# io-headers.net
KiCad netlist of a schematic drawn in Altium Designer
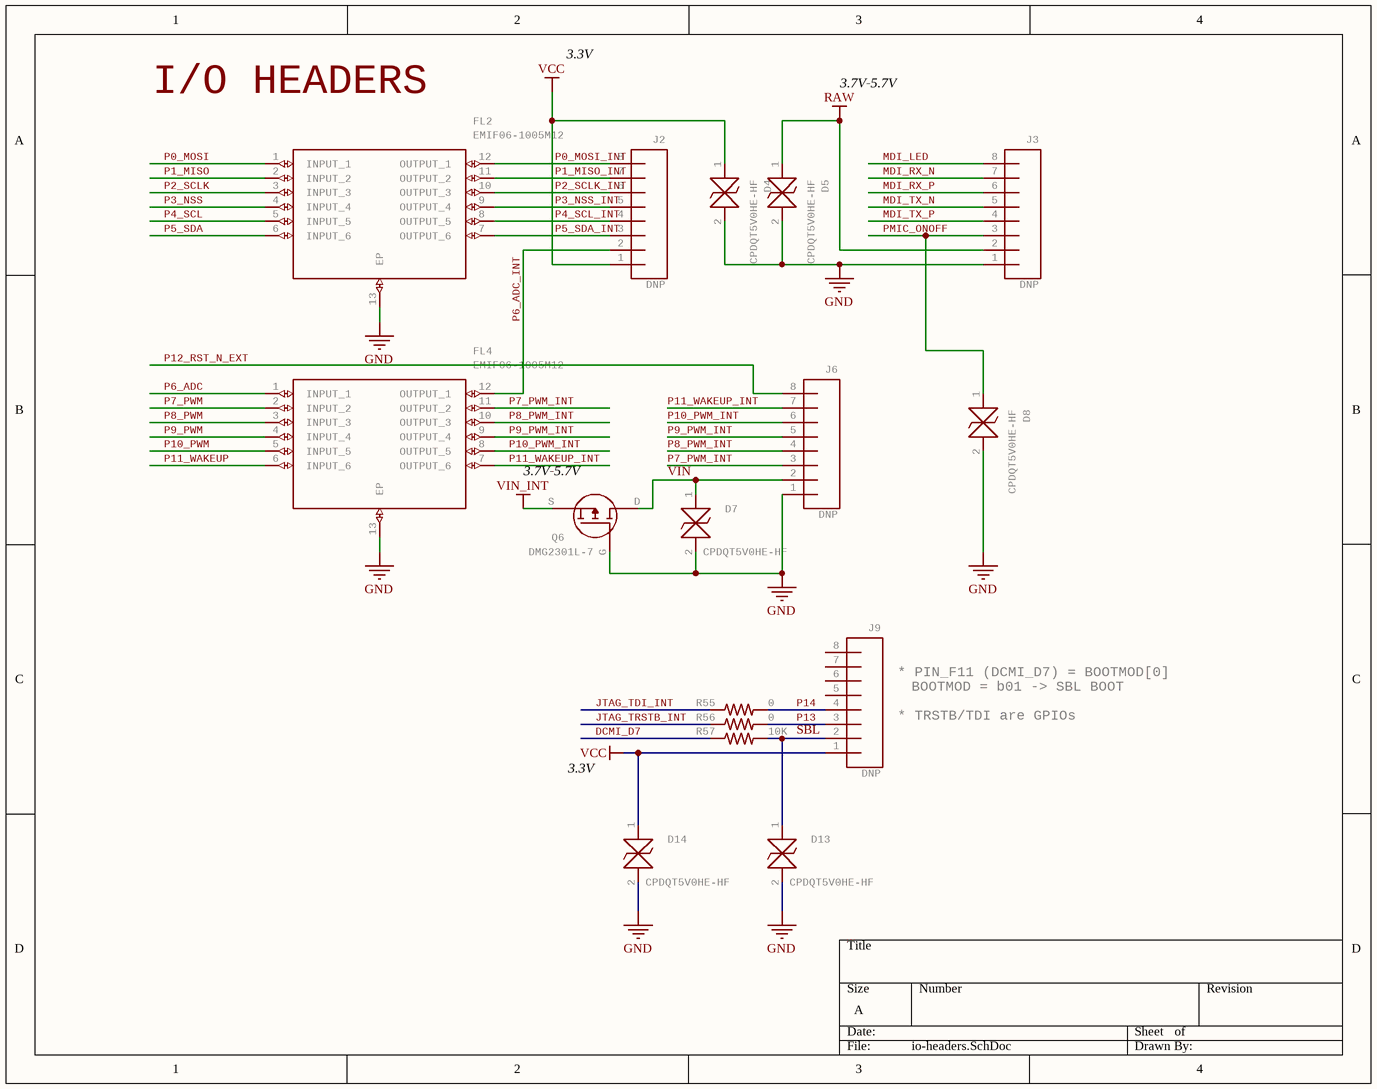
[diagram p0: io-headers.SchDoc]

(export (version "E")
  (design (tool "Eeschema 10.0.6"))
  (components
    (comp (ref "D4")
      (value "CPDQT5V0HE-HF")
      (footprint "CPDQT5V0HEHF")
      (description "ESD Suppressors / TVS Diodes DIODE ESD 5VWM 65W 0402/SOD-923F   Source:  Datasheet")
      (fields (field (name "MOUSER_PART_NUMBER") "MOUSER_PART_NUMBER"))
      (libsource (lib "rt10") (part "CPDQT5V0HE-HF"))
    )
    (comp (ref "D5")
      (value "CPDQT5V0HE-HF")
      (footprint "CPDQT5V0HEHF")
      (description "ESD Suppressors / TVS Diodes DIODE ESD 5VWM 65W 0402/SOD-923F   Source:  Datasheet")
      (fields (field (name "MOUSER_PART_NUMBER") "MOUSER_PART_NUMBER"))
      (libsource (lib "rt10") (part "CPDQT5V0HE-HF"))
    )
    (comp (ref "D7")
      (value "CPDQT5V0HE-HF")
      (footprint "CPDQT5V0HEHF")
      (description "ESD Suppressors / TVS Diodes DIODE ESD 5VWM 65W 0402/SOD-923F   Source:  Datasheet")
      (fields (field (name "MOUSER_PART_NUMBER") "MOUSER_PART_NUMBER"))
      (libsource (lib "rt10") (part "CPDQT5V0HE-HF"))
    )
    (comp (ref "D8")
      (value "CPDQT5V0HE-HF")
      (footprint "CPDQT5V0HEHF")
      (description "ESD Suppressors / TVS Diodes DIODE ESD 5VWM 65W 0402/SOD-923F   Source:  Datasheet")
      (fields (field (name "MOUSER_PART_NUMBER") "MOUSER_PART_NUMBER"))
      (libsource (lib "rt10") (part "CPDQT5V0HE-HF"))
    )
    (comp (ref "D13")
      (value "CPDQT5V0HE-HF")
      (footprint "CPDQT5V0HEHF")
      (description "ESD Suppressors / TVS Diodes DIODE ESD 5VWM 65W 0402/SOD-923F   Source:  Datasheet")
      (fields (field (name "MOUSER_PART_NUMBER") "MOUSER_PART_NUMBER"))
      (libsource (lib "rt10") (part "CPDQT5V0HE-HF"))
    )
    (comp (ref "D14")
      (value "CPDQT5V0HE-HF")
      (footprint "CPDQT5V0HEHF")
      (description "ESD Suppressors / TVS Diodes DIODE ESD 5VWM 65W 0402/SOD-923F   Source:  Datasheet")
      (fields (field (name "MOUSER_PART_NUMBER") "MOUSER_PART_NUMBER"))
      (libsource (lib "rt10") (part "CPDQT5V0HE-HF"))
    )
    (comp (ref "FL2")
      (value "EMIF06-1005M12")
      (footprint "SON40P150X250X65-13N")
      (description "EMI Filter Circuits 6lin lw cpcitnc EMI 45pF -35db @ 900MHz   Source:  Datasheet")
      (fields (field (name "MOUSER_PART_NUMBER") "511-EMIF06-1005M12"))
      (libsource (lib "rt10") (part "EMIF06-1005M12"))
    )
    (comp (ref "FL4")
      (value "EMIF06-1005M12")
      (footprint "SON40P150X250X65-13N")
      (description "EMI Filter Circuits 6lin lw cpcitnc EMI 45pF -35db @ 900MHz   Source:  Datasheet")
      (fields (field (name "MOUSER_PART_NUMBER") "511-EMIF06-1005M12"))
      (libsource (lib "rt10") (part "EMIF06-1005M12"))
    )
    (comp (ref "J2") (value "DNP") (footprint "1X08") (libsource (lib "rt10") (part "CONN_08{dblquote}")))
    (comp (ref "J3") (value "DNP") (footprint "1X08") (libsource (lib "rt10") (part "CONN_08{dblquote}")))
    (comp (ref "J6") (value "DNP") (footprint "1X08") (libsource (lib "rt10") (part "CONN_08{dblquote}")))
    (comp (ref "J9") (value "DNP") (footprint "1X08") (libsource (lib "rt10") (part "CONN_08{dblquote}")))
    (comp (ref "Q6")
      (value "DMG2301L-7")
      (footprint "SOT-23-3-FET")
      (libsource (lib "rt10") (part "DMG2301L-7"))
    )
    (comp (ref "R55")
      (value "0")
      (footprint "0402-RES")
      (description "ResistorBasic schematic elements and footprints for 0603, 1206, and PTH resistors.")
      (fields (field (name "MPN") "RC0402JR-070R"))
      (libsource (lib "rt10") (part "RESISTOR0402-RES"))
    )
    (comp (ref "R56")
      (value "0")
      (footprint "0402-RES")
      (description "ResistorBasic schematic elements and footprints for 0603, 1206, and PTH resistors.")
      (fields (field (name "MPN") "RC0402JR-070R"))
      (libsource (lib "rt10") (part "RESISTOR0402-RES"))
    )
    (comp (ref "R57")
      (value "10K")
      (footprint "0402-RES")
      (description "ResistorBasic schematic elements and footprints for 0603, 1206, and PTH resistors.")
      (fields (field (name "MPN") "AC0402FR-1310K"))
      (libsource (lib "rt10") (part "RESISTOR0402-RES"))
    )
  )
  (nets
    (net (code "1") (name "/DCMI_D7") (class "Default")
      (node (ref "R57") (pin "1") (pinfunction "1_1") (pintype "passive"))
    )
    (net (code "2") (name "/JTAG_TDI_INT") (class "Default")
      (node (ref "R55") (pin "1") (pinfunction "1_1") (pintype "passive"))
    )
    (net (code "3") (name "/JTAG_TRSTB_INT") (class "Default")
      (node (ref "R56") (pin "1") (pinfunction "1_1") (pintype "passive"))
    )
    (net (code "4") (name "/MDI_LED") (class "Default")
      (node (ref "J3") (pin "8") (pinfunction "8_8") (pintype "passive"))
    )
    (net (code "5") (name "/MDI_RX_N") (class "Default")
      (node (ref "J3") (pin "7") (pinfunction "7_7") (pintype "passive"))
    )
    (net (code "6") (name "/MDI_RX_P") (class "Default")
      (node (ref "J3") (pin "6") (pinfunction "6_6") (pintype "passive"))
    )
    (net (code "7") (name "/MDI_TX_N") (class "Default")
      (node (ref "J3") (pin "5") (pinfunction "5_5") (pintype "passive"))
    )
    (net (code "8") (name "/MDI_TX_P") (class "Default")
      (node (ref "J3") (pin "4") (pinfunction "4_4") (pintype "passive"))
    )
    (net (code "9") (name "/P0_MOSI") (class "Default")
      (node (ref "FL2") (pin "1") (pinfunction "INPUT_1_1") (pintype "bidirectional"))
    )
    (net (code "10") (name "/P0_MOSI_INT") (class "Default")
      (node (ref "FL2") (pin "12") (pinfunction "OUTPUT_1_12") (pintype "bidirectional"))
      (node (ref "J2") (pin "8") (pinfunction "8_8") (pintype "passive"))
    )
    (net (code "11") (name "/P1_MISO") (class "Default")
      (node (ref "FL2") (pin "2") (pinfunction "INPUT_2_2") (pintype "bidirectional"))
    )
    (net (code "12") (name "/P1_MISO_INT") (class "Default")
      (node (ref "FL2") (pin "11") (pinfunction "OUTPUT_2_11") (pintype "bidirectional"))
      (node (ref "J2") (pin "7") (pinfunction "7_7") (pintype "passive"))
    )
    (net (code "13") (name "/P2_SCLK") (class "Default")
      (node (ref "FL2") (pin "3") (pinfunction "INPUT_3_3") (pintype "bidirectional"))
    )
    (net (code "14") (name "/P2_SCLK_INT") (class "Default")
      (node (ref "FL2") (pin "10") (pinfunction "OUTPUT_3_10") (pintype "bidirectional"))
      (node (ref "J2") (pin "6") (pinfunction "6_6") (pintype "passive"))
    )
    (net (code "15") (name "/P3_NSS") (class "Default")
      (node (ref "FL2") (pin "4") (pinfunction "INPUT_4_4") (pintype "bidirectional"))
    )
    (net (code "16") (name "/P3_NSS_INT") (class "Default")
      (node (ref "FL2") (pin "9") (pinfunction "OUTPUT_4_9") (pintype "bidirectional"))
      (node (ref "J2") (pin "5") (pinfunction "5_5") (pintype "passive"))
    )
    (net (code "17") (name "/P4_SCL") (class "Default")
      (node (ref "FL2") (pin "5") (pinfunction "INPUT_5_5") (pintype "bidirectional"))
    )
    (net (code "18") (name "/P4_SCL_INT") (class "Default")
      (node (ref "FL2") (pin "8") (pinfunction "OUTPUT_5_8") (pintype "bidirectional"))
      (node (ref "J2") (pin "4") (pinfunction "4_4") (pintype "passive"))
    )
    (net (code "19") (name "/P5_SDA") (class "Default")
      (node (ref "FL2") (pin "6") (pinfunction "INPUT_6_6") (pintype "bidirectional"))
    )
    (net (code "20") (name "/P5_SDA_INT") (class "Default")
      (node (ref "FL2") (pin "7") (pinfunction "OUTPUT_6_7") (pintype "bidirectional"))
      (node (ref "J2") (pin "3") (pinfunction "3_3") (pintype "passive"))
    )
    (net (code "21") (name "/P6_ADC") (class "Default")
      (node (ref "FL4") (pin "1") (pinfunction "INPUT_1_1") (pintype "bidirectional"))
    )
    (net (code "22") (name "/P6_ADC_INT") (class "Default")
      (node (ref "FL4") (pin "12") (pinfunction "OUTPUT_1_12") (pintype "bidirectional"))
      (node (ref "J2") (pin "2") (pinfunction "2_2") (pintype "passive"))
    )
    (net (code "23") (name "/P7_PWM") (class "Default")
      (node (ref "FL4") (pin "2") (pinfunction "INPUT_2_2") (pintype "bidirectional"))
    )
    (net (code "24") (name "/P7_PWM_INT") (class "Default")
      (node (ref "FL4") (pin "11") (pinfunction "OUTPUT_2_11") (pintype "bidirectional"))
      (node (ref "J6") (pin "3") (pinfunction "3_3") (pintype "passive"))
    )
    (net (code "25") (name "/P8_PWM") (class "Default")
      (node (ref "FL4") (pin "3") (pinfunction "INPUT_3_3") (pintype "bidirectional"))
    )
    (net (code "26") (name "/P8_PWM_INT") (class "Default")
      (node (ref "FL4") (pin "10") (pinfunction "OUTPUT_3_10") (pintype "bidirectional"))
      (node (ref "J6") (pin "4") (pinfunction "4_4") (pintype "passive"))
    )
    (net (code "27") (name "/P9_PWM") (class "Default")
      (node (ref "FL4") (pin "4") (pinfunction "INPUT_4_4") (pintype "bidirectional"))
    )
    (net (code "28") (name "/P9_PWM_INT") (class "Default")
      (node (ref "FL4") (pin "9") (pinfunction "OUTPUT_4_9") (pintype "bidirectional"))
      (node (ref "J6") (pin "5") (pinfunction "5_5") (pintype "passive"))
    )
    (net (code "29") (name "/P10_PWM") (class "Default")
      (node (ref "FL4") (pin "5") (pinfunction "INPUT_5_5") (pintype "bidirectional"))
    )
    (net (code "30") (name "/P10_PWM_INT") (class "Default")
      (node (ref "FL4") (pin "8") (pinfunction "OUTPUT_5_8") (pintype "bidirectional"))
      (node (ref "J6") (pin "6") (pinfunction "6_6") (pintype "passive"))
    )
    (net (code "31") (name "/P11_WAKEUP") (class "Default")
      (node (ref "FL4") (pin "6") (pinfunction "INPUT_6_6") (pintype "bidirectional"))
    )
    (net (code "32") (name "/P11_WAKEUP_INT") (class "Default")
      (node (ref "FL4") (pin "7") (pinfunction "OUTPUT_6_7") (pintype "bidirectional"))
      (node (ref "J6") (pin "7") (pinfunction "7_7") (pintype "passive"))
    )
    (net (code "33") (name "/P12_RST_N_EXT") (class "Default")
      (node (ref "J6") (pin "8") (pinfunction "8_8") (pintype "passive"))
    )
    (net (code "34") (name "/P13") (class "Default")
      (node (ref "J9") (pin "3") (pinfunction "3_3") (pintype "passive"))
      (node (ref "R56") (pin "2") (pinfunction "2_2") (pintype "passive"))
    )
    (net (code "35") (name "/P14") (class "Default")
      (node (ref "J9") (pin "4") (pinfunction "4_4") (pintype "passive"))
      (node (ref "R55") (pin "2") (pinfunction "2_2") (pintype "passive"))
    )
    (net (code "36") (name "/PMIC_ONOFF") (class "Default")
      (node (ref "D8") (pin "1") (pinfunction "1_1") (pintype "bidirectional"))
      (node (ref "J3") (pin "3") (pinfunction "3_3") (pintype "passive"))
    )
    (net (code "37") (name "/SBL") (class "Default")
      (node (ref "D13") (pin "1") (pinfunction "1_1") (pintype "bidirectional"))
      (node (ref "J9") (pin "2") (pinfunction "2_2") (pintype "passive"))
      (node (ref "R57") (pin "2") (pinfunction "2_2") (pintype "passive"))
    )
    (net (code "38") (name "/VIN") (class "Default")
      (node (ref "D7") (pin "1") (pinfunction "1_1") (pintype "bidirectional"))
      (node (ref "J6") (pin "2") (pinfunction "2_2") (pintype "passive"))
      (node (ref "Q6") (pin "D") (pinfunction "D_D") (pintype "bidirectional"))
    )
    (net (code "39") (name "GND") (class "Default")
      (node (ref "D13") (pin "2") (pinfunction "2_2") (pintype "bidirectional"))
      (node (ref "D14") (pin "2") (pinfunction "2_2") (pintype "bidirectional"))
      (node (ref "D4") (pin "2") (pinfunction "2_2") (pintype "bidirectional"))
      (node (ref "D5") (pin "2") (pinfunction "2_2") (pintype "bidirectional"))
      (node (ref "D7") (pin "2") (pinfunction "2_2") (pintype "bidirectional"))
      (node (ref "D8") (pin "2") (pinfunction "2_2") (pintype "bidirectional"))
      (node (ref "FL2") (pin "13") (pinfunction "EP_13") (pintype "bidirectional"))
      (node (ref "FL4") (pin "13") (pinfunction "EP_13") (pintype "bidirectional"))
      (node (ref "J3") (pin "1") (pinfunction "1_1") (pintype "passive"))
      (node (ref "J6") (pin "1") (pinfunction "1_1") (pintype "passive"))
      (node (ref "Q6") (pin "G") (pinfunction "G_G") (pintype "bidirectional"))
    )
    (net (code "40") (name "RAW") (class "Default")
      (node (ref "D5") (pin "1") (pinfunction "1_1") (pintype "bidirectional"))
      (node (ref "J3") (pin "2") (pinfunction "2_2") (pintype "passive"))
    )
    (net (code "41") (name "VCC") (class "Default")
      (node (ref "D14") (pin "1") (pinfunction "1_1") (pintype "bidirectional"))
      (node (ref "D4") (pin "1") (pinfunction "1_1") (pintype "bidirectional"))
      (node (ref "J2") (pin "1") (pinfunction "1_1") (pintype "passive"))
      (node (ref "J9") (pin "1") (pinfunction "1_1") (pintype "passive"))
    )
    (net (code "42") (name "VIN_INT") (class "Default")
      (node (ref "Q6") (pin "S") (pinfunction "S_S") (pintype "bidirectional"))
    )
    (net (code "43") (name "unconnected-(J9-Pad5)") (class "Default")
      (node (ref "J9") (pin "5") (pinfunction "5_5") (pintype "passive"))
    )
    (net (code "44") (name "unconnected-(J9-Pad6)") (class "Default")
      (node (ref "J9") (pin "6") (pinfunction "6_6") (pintype "passive"))
    )
    (net (code "45") (name "unconnected-(J9-Pad7)") (class "Default")
      (node (ref "J9") (pin "7") (pinfunction "7_7") (pintype "passive"))
    )
    (net (code "46") (name "unconnected-(J9-Pad8)") (class "Default")
      (node (ref "J9") (pin "8") (pinfunction "8_8") (pintype "passive"))
    )
  )
)
